# Demo_Board_2-_Schematic.net
KiCad netlist of a schematic drawn in Altium Designer
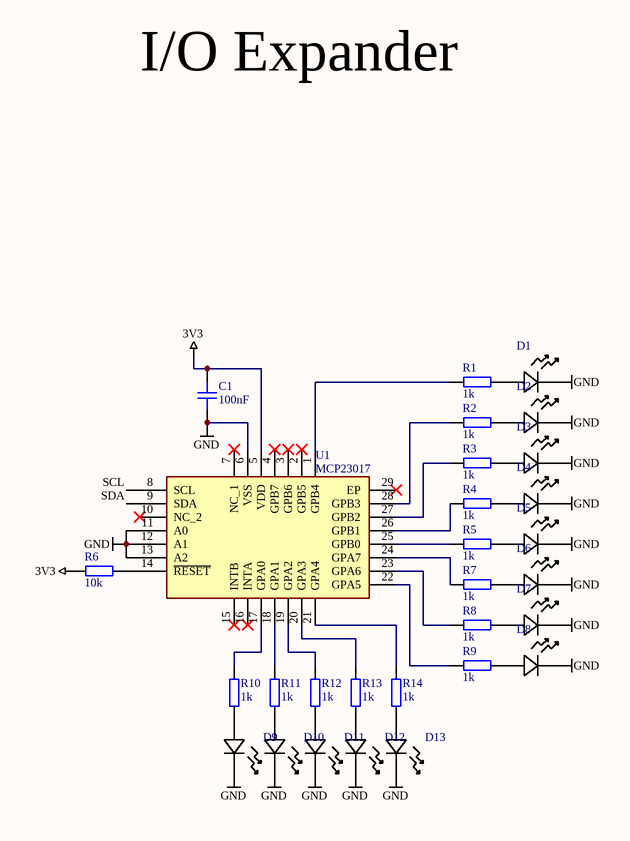
[diagram p0: Demo Board 2- Schematic.SchDoc]

(export (version "E")
  (design (tool "Eeschema 10.0.6"))
  (components
    (comp (ref "C1")
      (value "100nF")
      (footprint "CAP_0603")
      (description "Capacitor SMD 0603")
      (libsource (lib "Auer Library") (part "CAP_0603"))
    )
    (comp (ref "D1")
      (value "SML-310VTT86")
      (footprint "LED_SML-310_ROM")
      (description "Description")
      (fields (field (name "COPYRIGHT") "Copyright (C) 2025 Ultra Librarian. All rights reserved."))
      (libsource (lib "SML-310VTT86") (part "SML-310VTT86"))
    )
    (comp (ref "D2")
      (value "SML-310VTT86")
      (footprint "LED_SML-310_ROM")
      (description "Description")
      (fields (field (name "COPYRIGHT") "Copyright (C) 2025 Ultra Librarian. All rights reserved."))
      (libsource (lib "SML-310VTT86") (part "SML-310VTT86"))
    )
    (comp (ref "D3")
      (value "SML-310VTT86")
      (footprint "LED_SML-310_ROM")
      (description "Description")
      (fields (field (name "COPYRIGHT") "Copyright (C) 2025 Ultra Librarian. All rights reserved."))
      (libsource (lib "SML-310VTT86") (part "SML-310VTT86"))
    )
    (comp (ref "D4")
      (value "SML-310VTT86")
      (footprint "LED_SML-310_ROM")
      (description "Description")
      (fields (field (name "COPYRIGHT") "Copyright (C) 2025 Ultra Librarian. All rights reserved."))
      (libsource (lib "SML-310VTT86") (part "SML-310VTT86"))
    )
    (comp (ref "D5")
      (value "SML-310VTT86")
      (footprint "LED_SML-310_ROM")
      (description "Description")
      (fields (field (name "COPYRIGHT") "Copyright (C) 2025 Ultra Librarian. All rights reserved."))
      (libsource (lib "SML-310VTT86") (part "SML-310VTT86"))
    )
    (comp (ref "D6")
      (value "SML-310VTT86")
      (footprint "LED_SML-310_ROM")
      (description "Description")
      (fields (field (name "COPYRIGHT") "Copyright (C) 2025 Ultra Librarian. All rights reserved."))
      (libsource (lib "SML-310VTT86") (part "SML-310VTT86"))
    )
    (comp (ref "D7")
      (value "SML-310VTT86")
      (footprint "LED_SML-310_ROM")
      (description "Description")
      (fields (field (name "COPYRIGHT") "Copyright (C) 2025 Ultra Librarian. All rights reserved."))
      (libsource (lib "SML-310VTT86") (part "SML-310VTT86"))
    )
    (comp (ref "D8")
      (value "SML-310VTT86")
      (footprint "LED_SML-310_ROM")
      (description "Description")
      (fields (field (name "COPYRIGHT") "Copyright (C) 2025 Ultra Librarian. All rights reserved."))
      (libsource (lib "SML-310VTT86") (part "SML-310VTT86"))
    )
    (comp (ref "D9")
      (value "SML-310VTT86")
      (footprint "LED_SML-310_ROM")
      (description "Description")
      (fields (field (name "COPYRIGHT") "Copyright (C) 2025 Ultra Librarian. All rights reserved."))
      (libsource (lib "SML-310VTT86") (part "SML-310VTT86"))
    )
    (comp (ref "D10")
      (value "SML-310VTT86")
      (footprint "LED_SML-310_ROM")
      (description "Description")
      (fields (field (name "COPYRIGHT") "Copyright (C) 2025 Ultra Librarian. All rights reserved."))
      (libsource (lib "SML-310VTT86") (part "SML-310VTT86"))
    )
    (comp (ref "D11")
      (value "SML-310VTT86")
      (footprint "LED_SML-310_ROM")
      (description "Description")
      (fields (field (name "COPYRIGHT") "Copyright (C) 2025 Ultra Librarian. All rights reserved."))
      (libsource (lib "SML-310VTT86") (part "SML-310VTT86"))
    )
    (comp (ref "D12")
      (value "SML-310VTT86")
      (footprint "LED_SML-310_ROM")
      (description "Description")
      (fields (field (name "COPYRIGHT") "Copyright (C) 2025 Ultra Librarian. All rights reserved."))
      (libsource (lib "SML-310VTT86") (part "SML-310VTT86"))
    )
    (comp (ref "D13")
      (value "SML-310VTT86")
      (footprint "LED_SML-310_ROM")
      (description "Description")
      (fields (field (name "COPYRIGHT") "Copyright (C) 2025 Ultra Librarian. All rights reserved."))
      (libsource (lib "SML-310VTT86") (part "SML-310VTT86"))
    )
    (comp (ref "R1")
      (value "1k")
      (footprint "RES_0603")
      (description "Resistor SMD 0603")
      (libsource (lib "Auer Library") (part "RES_0603"))
    )
    (comp (ref "R2")
      (value "1k")
      (footprint "RES_0603")
      (description "Resistor SMD 0603")
      (libsource (lib "Auer Library") (part "RES_0603"))
    )
    (comp (ref "R3")
      (value "1k")
      (footprint "RES_0603")
      (description "Resistor SMD 0603")
      (libsource (lib "Auer Library") (part "RES_0603"))
    )
    (comp (ref "R4")
      (value "1k")
      (footprint "RES_0603")
      (description "Resistor SMD 0603")
      (libsource (lib "Auer Library") (part "RES_0603"))
    )
    (comp (ref "R5")
      (value "1k")
      (footprint "RES_0603")
      (description "Resistor SMD 0603")
      (libsource (lib "Auer Library") (part "RES_0603"))
    )
    (comp (ref "R6")
      (value "10k")
      (footprint "RES_0603")
      (description "Resistor SMD 0603")
      (libsource (lib "Auer Library") (part "RES_0603"))
    )
    (comp (ref "R7")
      (value "1k")
      (footprint "RES_0603")
      (description "Resistor SMD 0603")
      (libsource (lib "Auer Library") (part "RES_0603"))
    )
    (comp (ref "R8")
      (value "1k")
      (footprint "RES_0603")
      (description "Resistor SMD 0603")
      (libsource (lib "Auer Library") (part "RES_0603"))
    )
    (comp (ref "R9")
      (value "1k")
      (footprint "RES_0603")
      (description "Resistor SMD 0603")
      (libsource (lib "Auer Library") (part "RES_0603"))
    )
    (comp (ref "R10")
      (value "1k")
      (footprint "RES_0603")
      (description "Resistor SMD 0603")
      (libsource (lib "Auer Library") (part "RES_0603"))
    )
    (comp (ref "R11")
      (value "1k")
      (footprint "RES_0603")
      (description "Resistor SMD 0603")
      (libsource (lib "Auer Library") (part "RES_0603"))
    )
    (comp (ref "R12")
      (value "1k")
      (footprint "RES_0603")
      (description "Resistor SMD 0603")
      (libsource (lib "Auer Library") (part "RES_0603"))
    )
    (comp (ref "R13")
      (value "1k")
      (footprint "RES_0603")
      (description "Resistor SMD 0603")
      (libsource (lib "Auer Library") (part "RES_0603"))
    )
    (comp (ref "R14")
      (value "1k")
      (footprint "RES_0603")
      (description "Resistor SMD 0603")
      (libsource (lib "Auer Library") (part "RES_0603"))
    )
    (comp (ref "U1")
      (value "MCP23017")
      (footprint "SamacSys:QFN65P600X600X100-29N-D")
      (description "Integrated Circuit")
      (fields
        (field (name "MANUFACTURER_PART_NUMBER") "MCP23017-E/ML")
        (field (name "MOUSER PART NUMBER") "579-MCP23017-E/ML")
      )
      (libsource (lib "*") (part "MCP23017-E_ML"))
    )
  )
  (nets
    (net (code "1") (name "/SCL") (class "Default")
      (node (ref "U1") (pin "8") (pinfunction "SCL_8") (pintype "passive"))
    )
    (net (code "2") (name "/SDA") (class "Default")
      (node (ref "U1") (pin "9") (pinfunction "SDA_9") (pintype "passive"))
    )
    (net (code "3") (name "3V3") (class "Default")
      (node (ref "C1") (pin "2") (pinfunction "2_2") (pintype "passive"))
      (node (ref "R6") (pin "1") (pinfunction "1_1") (pintype "passive"))
      (node (ref "U1") (pin "5") (pinfunction "VDD_5") (pintype "passive"))
    )
    (net (code "4") (name "GND") (class "Default")
      (node (ref "C1") (pin "1") (pinfunction "1_1") (pintype "passive"))
      (node (ref "D1") (pin "1") (pinfunction "1_1") (pintype "passive"))
      (node (ref "D10") (pin "1") (pinfunction "1_1") (pintype "passive"))
      (node (ref "D11") (pin "1") (pinfunction "1_1") (pintype "passive"))
      (node (ref "D12") (pin "1") (pinfunction "1_1") (pintype "passive"))
      (node (ref "D13") (pin "1") (pinfunction "1_1") (pintype "passive"))
      (node (ref "D2") (pin "1") (pinfunction "1_1") (pintype "passive"))
      (node (ref "D3") (pin "1") (pinfunction "1_1") (pintype "passive"))
      (node (ref "D4") (pin "1") (pinfunction "1_1") (pintype "passive"))
      (node (ref "D5") (pin "1") (pinfunction "1_1") (pintype "passive"))
      (node (ref "D6") (pin "1") (pinfunction "1_1") (pintype "passive"))
      (node (ref "D7") (pin "1") (pinfunction "1_1") (pintype "passive"))
      (node (ref "D8") (pin "1") (pinfunction "1_1") (pintype "passive"))
      (node (ref "D9") (pin "1") (pinfunction "1_1") (pintype "passive"))
      (node (ref "U1") (pin "11") (pinfunction "A0_11") (pintype "passive"))
      (node (ref "U1") (pin "12") (pinfunction "A1_12") (pintype "passive"))
      (node (ref "U1") (pin "13") (pinfunction "A2_13") (pintype "passive"))
      (node (ref "U1") (pin "6") (pinfunction "VSS_6") (pintype "passive"))
    )
    (net (code "5") (name "Net-(D1-Pad2)") (class "Default")
      (node (ref "D1") (pin "2") (pinfunction "2_2") (pintype "passive"))
      (node (ref "R1") (pin "2") (pinfunction "2_2") (pintype "passive"))
    )
    (net (code "6") (name "Net-(D2-Pad2)") (class "Default")
      (node (ref "D2") (pin "2") (pinfunction "2_2") (pintype "passive"))
      (node (ref "R2") (pin "2") (pinfunction "2_2") (pintype "passive"))
    )
    (net (code "7") (name "Net-(D3-Pad2)") (class "Default")
      (node (ref "D3") (pin "2") (pinfunction "2_2") (pintype "passive"))
      (node (ref "R3") (pin "2") (pinfunction "2_2") (pintype "passive"))
    )
    (net (code "8") (name "Net-(D4-Pad2)") (class "Default")
      (node (ref "D4") (pin "2") (pinfunction "2_2") (pintype "passive"))
      (node (ref "R4") (pin "2") (pinfunction "2_2") (pintype "passive"))
    )
    (net (code "9") (name "Net-(D5-Pad2)") (class "Default")
      (node (ref "D5") (pin "2") (pinfunction "2_2") (pintype "passive"))
      (node (ref "R5") (pin "2") (pinfunction "2_2") (pintype "passive"))
    )
    (net (code "10") (name "Net-(D6-Pad2)") (class "Default")
      (node (ref "D6") (pin "2") (pinfunction "2_2") (pintype "passive"))
      (node (ref "R7") (pin "2") (pinfunction "2_2") (pintype "passive"))
    )
    (net (code "11") (name "Net-(D7-Pad2)") (class "Default")
      (node (ref "D7") (pin "2") (pinfunction "2_2") (pintype "passive"))
      (node (ref "R8") (pin "2") (pinfunction "2_2") (pintype "passive"))
    )
    (net (code "12") (name "Net-(D8-Pad2)") (class "Default")
      (node (ref "D8") (pin "2") (pinfunction "2_2") (pintype "passive"))
      (node (ref "R9") (pin "2") (pinfunction "2_2") (pintype "passive"))
    )
    (net (code "13") (name "Net-(D9-Pad2)") (class "Default")
      (node (ref "D9") (pin "2") (pinfunction "2_2") (pintype "passive"))
      (node (ref "R10") (pin "2") (pinfunction "2_2") (pintype "passive"))
    )
    (net (code "14") (name "Net-(D10-Pad2)") (class "Default")
      (node (ref "D10") (pin "2") (pinfunction "2_2") (pintype "passive"))
      (node (ref "R11") (pin "2") (pinfunction "2_2") (pintype "passive"))
    )
    (net (code "15") (name "Net-(D11-Pad2)") (class "Default")
      (node (ref "D11") (pin "2") (pinfunction "2_2") (pintype "passive"))
      (node (ref "R12") (pin "2") (pinfunction "2_2") (pintype "passive"))
    )
    (net (code "16") (name "Net-(D12-Pad2)") (class "Default")
      (node (ref "D12") (pin "2") (pinfunction "2_2") (pintype "passive"))
      (node (ref "R13") (pin "2") (pinfunction "2_2") (pintype "passive"))
    )
    (net (code "17") (name "Net-(D13-Pad2)") (class "Default")
      (node (ref "D13") (pin "2") (pinfunction "2_2") (pintype "passive"))
      (node (ref "R14") (pin "2") (pinfunction "2_2") (pintype "passive"))
    )
    (net (code "18") (name "Net-(U1-GPA0)") (class "Default")
      (node (ref "R10") (pin "1") (pinfunction "1_1") (pintype "passive"))
      (node (ref "U1") (pin "17") (pinfunction "GPA0_17") (pintype "passive"))
    )
    (net (code "19") (name "Net-(U1-GPA1)") (class "Default")
      (node (ref "R11") (pin "1") (pinfunction "1_1") (pintype "passive"))
      (node (ref "U1") (pin "18") (pinfunction "GPA1_18") (pintype "passive"))
    )
    (net (code "20") (name "Net-(U1-GPA2)") (class "Default")
      (node (ref "R12") (pin "1") (pinfunction "1_1") (pintype "passive"))
      (node (ref "U1") (pin "19") (pinfunction "GPA2_19") (pintype "passive"))
    )
    (net (code "21") (name "Net-(U1-GPA3)") (class "Default")
      (node (ref "R13") (pin "1") (pinfunction "1_1") (pintype "passive"))
      (node (ref "U1") (pin "20") (pinfunction "GPA3_20") (pintype "passive"))
    )
    (net (code "22") (name "Net-(U1-GPA4)") (class "Default")
      (node (ref "R14") (pin "1") (pinfunction "1_1") (pintype "passive"))
      (node (ref "U1") (pin "21") (pinfunction "GPA4_21") (pintype "passive"))
    )
    (net (code "23") (name "Net-(U1-GPA5)") (class "Default")
      (node (ref "R9") (pin "1") (pinfunction "1_1") (pintype "passive"))
      (node (ref "U1") (pin "22") (pinfunction "GPA5_22") (pintype "passive"))
    )
    (net (code "24") (name "Net-(U1-GPA6)") (class "Default")
      (node (ref "R8") (pin "1") (pinfunction "1_1") (pintype "passive"))
      (node (ref "U1") (pin "23") (pinfunction "GPA6_23") (pintype "passive"))
    )
    (net (code "25") (name "Net-(U1-GPA7)") (class "Default")
      (node (ref "R7") (pin "1") (pinfunction "1_1") (pintype "passive"))
      (node (ref "U1") (pin "24") (pinfunction "GPA7_24") (pintype "passive"))
    )
    (net (code "26") (name "Net-(U1-GPB0)") (class "Default")
      (node (ref "R5") (pin "1") (pinfunction "1_1") (pintype "passive"))
      (node (ref "U1") (pin "25") (pinfunction "GPB0_25") (pintype "passive"))
    )
    (net (code "27") (name "Net-(U1-GPB1)") (class "Default")
      (node (ref "R4") (pin "1") (pinfunction "1_1") (pintype "passive"))
      (node (ref "U1") (pin "26") (pinfunction "GPB1_26") (pintype "passive"))
    )
    (net (code "28") (name "Net-(U1-GPB2)") (class "Default")
      (node (ref "R3") (pin "1") (pinfunction "1_1") (pintype "passive"))
      (node (ref "U1") (pin "27") (pinfunction "GPB2_27") (pintype "passive"))
    )
    (net (code "29") (name "Net-(U1-GPB3)") (class "Default")
      (node (ref "R2") (pin "1") (pinfunction "1_1") (pintype "passive"))
      (node (ref "U1") (pin "28") (pinfunction "GPB3_28") (pintype "passive"))
    )
    (net (code "30") (name "Net-(U1-GPB4)") (class "Default")
      (node (ref "R1") (pin "1") (pinfunction "1_1") (pintype "passive"))
      (node (ref "U1") (pin "1") (pinfunction "GPB4_1") (pintype "passive"))
    )
    (net (code "31") (name "Net-(U1-~{RESET})") (class "Default")
      (node (ref "R6") (pin "2") (pinfunction "2_2") (pintype "passive"))
      (node (ref "U1") (pin "14") (pinfunction "~{RESET}_14") (pintype "passive"))
    )
    (net (code "32") (name "unconnected-(U1-EP-Pad29)") (class "Default")
      (node (ref "U1") (pin "29") (pinfunction "EP_29") (pintype "passive+no_connect"))
    )
    (net (code "33") (name "unconnected-(U1-GPB5-Pad2)") (class "Default")
      (node (ref "U1") (pin "2") (pinfunction "GPB5_2") (pintype "passive+no_connect"))
    )
    (net (code "34") (name "unconnected-(U1-GPB6-Pad3)") (class "Default")
      (node (ref "U1") (pin "3") (pinfunction "GPB6_3") (pintype "passive+no_connect"))
    )
    (net (code "35") (name "unconnected-(U1-GPB7-Pad4)") (class "Default")
      (node (ref "U1") (pin "4") (pinfunction "GPB7_4") (pintype "passive+no_connect"))
    )
    (net (code "36") (name "unconnected-(U1-INTA-Pad16)") (class "Default")
      (node (ref "U1") (pin "16") (pinfunction "INTA_16") (pintype "passive+no_connect"))
    )
    (net (code "37") (name "unconnected-(U1-INTB-Pad15)") (class "Default")
      (node (ref "U1") (pin "15") (pinfunction "INTB_15") (pintype "passive+no_connect"))
    )
    (net (code "38") (name "unconnected-(U1-NC_1-Pad7)") (class "Default")
      (node (ref "U1") (pin "7") (pinfunction "NC_1_7") (pintype "passive+no_connect"))
    )
    (net (code "39") (name "unconnected-(U1-NC_2-Pad10)") (class "Default")
      (node (ref "U1") (pin "10") (pinfunction "NC_2_10") (pintype "passive+no_connect"))
    )
  )
)
